# SNES_TST_Sheet3.net
KiCad netlist of a schematic drawn in Altium Designer
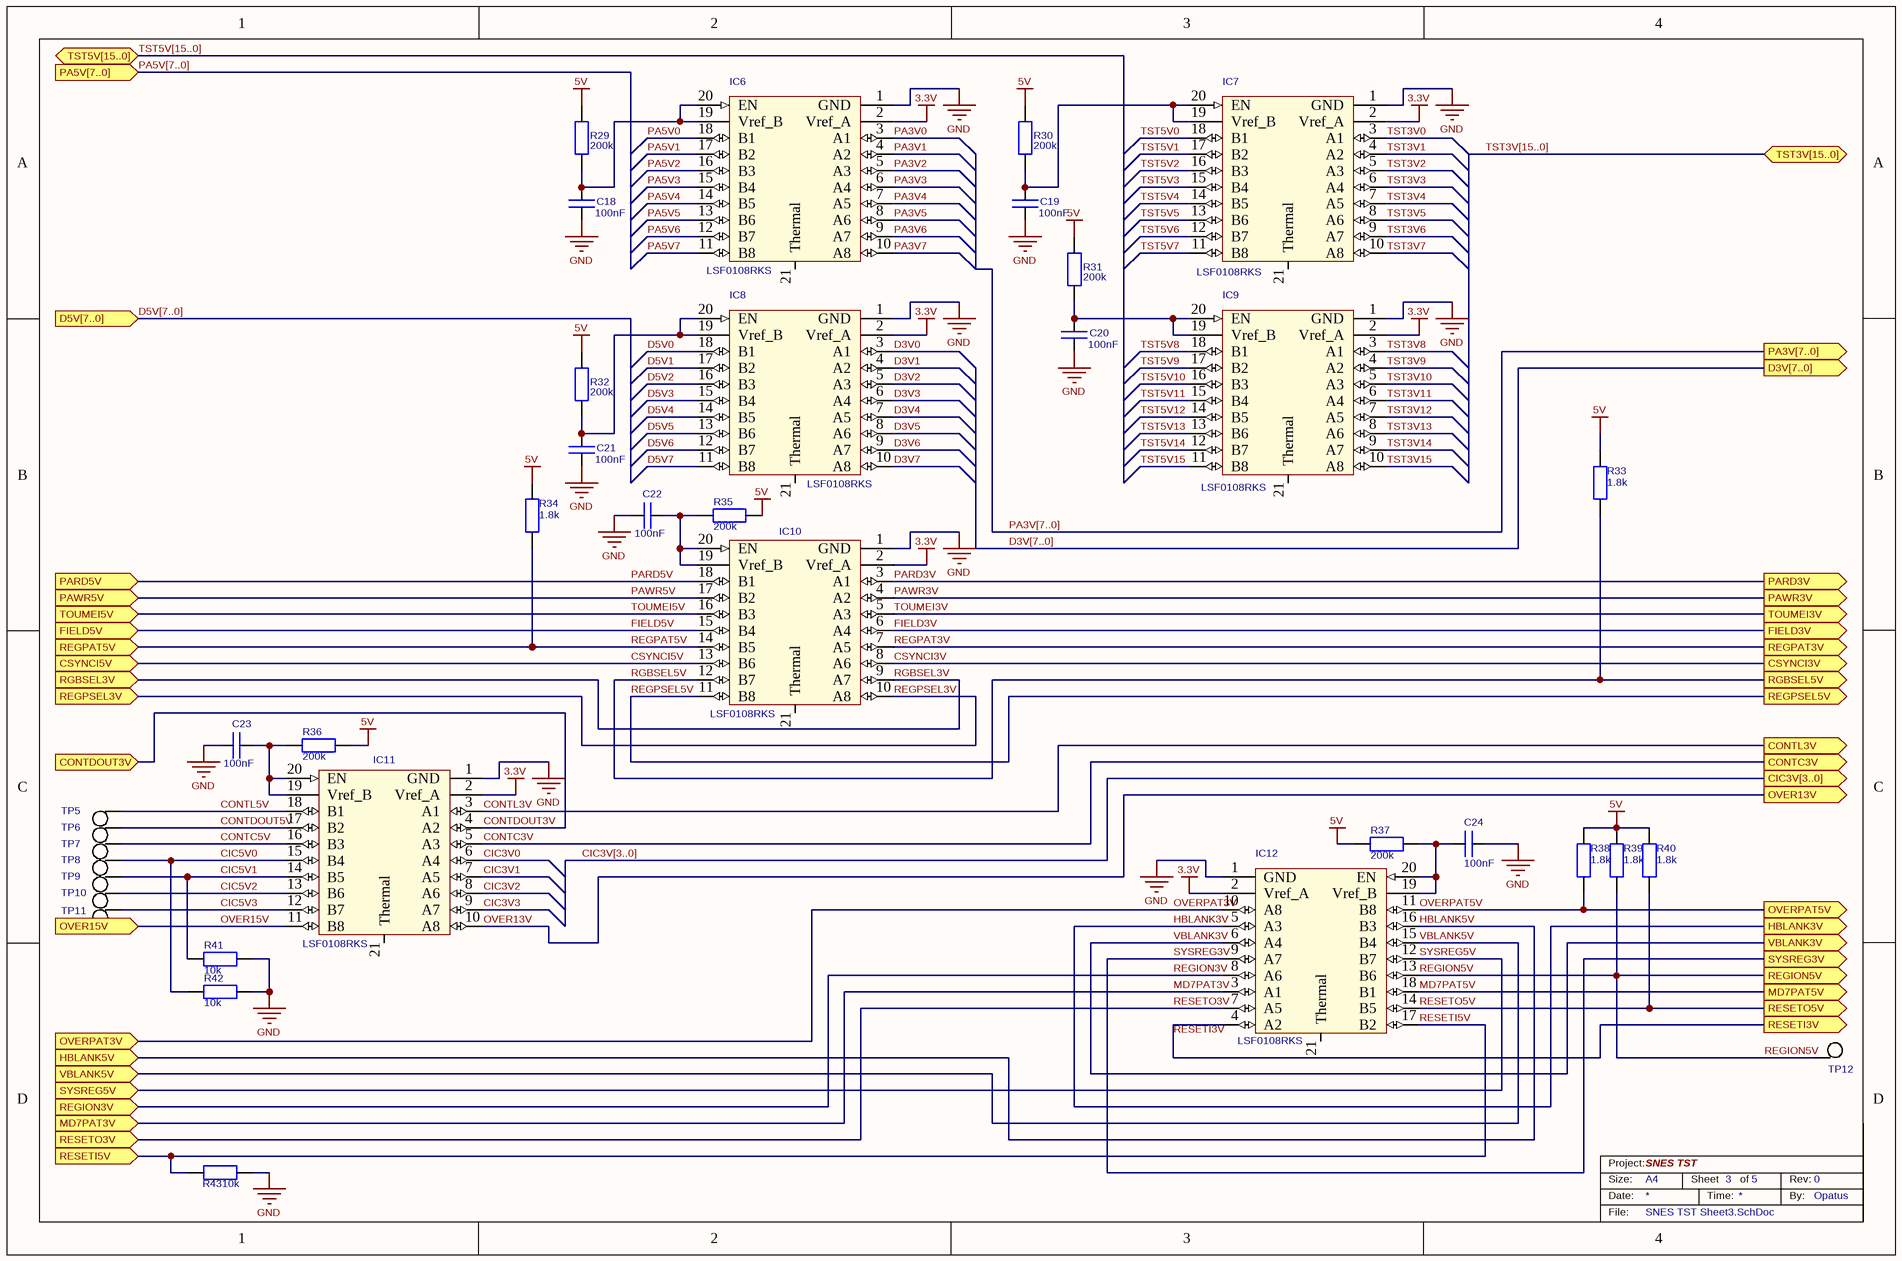
[diagram p0: SNES TST Sheet3.SchDoc]

(export (version "E")
  (design (tool "Eeschema 10.0.6"))
  (components
    (comp (ref "C18")
      (value "100nF")
      (footprint "Cap_0402_Chip")
      (fields (field (name "TOLERANCE") "+-20%"))
      (libsource (lib "PCB") (part "Capacitor"))
    )
    (comp (ref "C19")
      (value "100nF")
      (footprint "Cap_0402_Chip")
      (fields (field (name "TOLERANCE") "+-20%"))
      (libsource (lib "PCB") (part "Capacitor"))
    )
    (comp (ref "C20")
      (value "100nF")
      (footprint "Cap_0402_Chip")
      (fields (field (name "TOLERANCE") "+-20%"))
      (libsource (lib "PCB") (part "Capacitor"))
    )
    (comp (ref "C21")
      (value "100nF")
      (footprint "Cap_0402_Chip")
      (fields (field (name "TOLERANCE") "+-20%"))
      (libsource (lib "PCB") (part "Capacitor"))
    )
    (comp (ref "C22")
      (value "100nF")
      (footprint "Cap_0402_Chip")
      (fields (field (name "TOLERANCE") "+-20%"))
      (libsource (lib "PCB") (part "Capacitor"))
    )
    (comp (ref "C23")
      (value "100nF")
      (footprint "Cap_0402_Chip")
      (fields (field (name "TOLERANCE") "+-20%"))
      (libsource (lib "PCB") (part "Capacitor"))
    )
    (comp (ref "C24")
      (value "100nF")
      (footprint "Cap_0402_Chip")
      (fields (field (name "TOLERANCE") "+-20%"))
      (libsource (lib "PCB") (part "Capacitor"))
    )
    (comp (ref "IC6")
      (value "LSF0108")
      (footprint "VQFN20")
      (description "8-bit level shifter")
      (fields (field (name "MANUFACTURER_PART_NUMBER") "LSF0108RKS"))
      (libsource (lib "PCB") (part "LSF0108DCUR"))
    )
    (comp (ref "IC7")
      (value "LSF0108")
      (footprint "VQFN20")
      (description "8-bit level shifter")
      (fields (field (name "MANUFACTURER_PART_NUMBER") "LSF0108RKS"))
      (libsource (lib "PCB") (part "LSF0108DCUR"))
    )
    (comp (ref "IC8")
      (value "LSF0108")
      (footprint "VQFN20")
      (description "8-bit level shifter")
      (fields (field (name "MANUFACTURER_PART_NUMBER") "LSF0108RKS"))
      (libsource (lib "PCB") (part "LSF0108DCUR"))
    )
    (comp (ref "IC9")
      (value "LSF0108")
      (footprint "VQFN20")
      (description "8-bit level shifter")
      (fields (field (name "MANUFACTURER_PART_NUMBER") "LSF0108RKS"))
      (libsource (lib "PCB") (part "LSF0108DCUR"))
    )
    (comp (ref "IC10")
      (value "LSF0108")
      (footprint "VQFN20")
      (description "8-bit level shifter")
      (fields (field (name "MANUFACTURER_PART_NUMBER") "LSF0108RKS"))
      (libsource (lib "PCB") (part "LSF0108DCUR"))
    )
    (comp (ref "IC11")
      (value "LSF0108")
      (footprint "VQFN20")
      (description "8-bit level shifter")
      (fields (field (name "MANUFACTURER_PART_NUMBER") "LSF0108RKS"))
      (libsource (lib "PCB") (part "LSF0108DCUR"))
    )
    (comp (ref "IC12")
      (value "LSF0108")
      (footprint "VQFN20")
      (description "8-bit level shifter")
      (fields (field (name "MANUFACTURER_PART_NUMBER") "LSF0108RKS"))
      (libsource (lib "") (part "LSF0108DCUR_1"))
    )
    (comp (ref "R29")
      (value "200k")
      (footprint "Res_0402_Chip")
      (fields (field (name "TOLERANCE") "+-1%"))
      (libsource (lib "") (part "R_1"))
    )
    (comp (ref "R30")
      (value "200k")
      (footprint "Res_0402_Chip")
      (fields (field (name "TOLERANCE") "+-1%"))
      (libsource (lib "") (part "R_1"))
    )
    (comp (ref "R31")
      (value "200k")
      (footprint "Res_0402_Chip")
      (fields (field (name "TOLERANCE") "+-1%"))
      (libsource (lib "") (part "R_1"))
    )
    (comp (ref "R32")
      (value "200k")
      (footprint "Res_0402_Chip")
      (fields (field (name "TOLERANCE") "+-1%"))
      (libsource (lib "") (part "R_1"))
    )
    (comp (ref "R33")
      (value "1.8k")
      (footprint "Res_0402_Chip")
      (fields (field (name "TOLERANCE") "+-1%"))
      (libsource (lib "") (part "R_2"))
    )
    (comp (ref "R34")
      (value "1.8k")
      (footprint "Res_0402_Chip")
      (fields (field (name "TOLERANCE") "+-1%"))
      (libsource (lib "") (part "R_2"))
    )
    (comp (ref "R35")
      (value "200k")
      (footprint "Res_0402_Chip")
      (fields (field (name "TOLERANCE") "+-1%"))
      (libsource (lib "PCB") (part "R"))
    )
    (comp (ref "R36")
      (value "200k")
      (footprint "Res_0402_Chip")
      (fields (field (name "TOLERANCE") "+-1%"))
      (libsource (lib "PCB") (part "R"))
    )
    (comp (ref "R37")
      (value "200k")
      (footprint "Res_0402_Chip")
      (fields (field (name "TOLERANCE") "+-1%"))
      (libsource (lib "PCB") (part "R"))
    )
    (comp (ref "R38")
      (value "1.8k")
      (footprint "Res_0402_Chip")
      (fields (field (name "TOLERANCE") "+-1%"))
      (libsource (lib "") (part "R_2"))
    )
    (comp (ref "R39")
      (value "1.8k")
      (footprint "Res_0402_Chip")
      (fields (field (name "TOLERANCE") "+-1%"))
      (libsource (lib "") (part "R_2"))
    )
    (comp (ref "R40")
      (value "1.8k")
      (footprint "Res_0402_Chip")
      (fields (field (name "TOLERANCE") "+-1%"))
      (libsource (lib "") (part "R_2"))
    )
    (comp (ref "R41")
      (value "10k")
      (footprint "Res_0402_Chip")
      (fields (field (name "TOLERANCE") "+-1%"))
      (libsource (lib "PCB") (part "R"))
    )
    (comp (ref "R42")
      (value "10k")
      (footprint "Res_0402_Chip")
      (fields (field (name "TOLERANCE") "+-1%"))
      (libsource (lib "PCB") (part "R"))
    )
    (comp (ref "R43")
      (value "10k")
      (footprint "Res_0402_Chip")
      (fields (field (name "TOLERANCE") "+-1%"))
      (libsource (lib "") (part "R_3"))
    )
    (comp (ref "TP5")
      (value "Pin Connector")
      (footprint "Pin Connector Small")
      (libsource (lib "PCB") (part "Pin Connector"))
    )
    (comp (ref "TP6")
      (value "Pin Connector")
      (footprint "Pin Connector Small")
      (libsource (lib "PCB") (part "Pin Connector"))
    )
    (comp (ref "TP7")
      (value "Pin Connector")
      (footprint "Pin Connector Small")
      (libsource (lib "PCB") (part "Pin Connector"))
    )
    (comp (ref "TP8")
      (value "Pin Connector")
      (footprint "Pin Connector Small")
      (libsource (lib "PCB") (part "Pin Connector"))
    )
    (comp (ref "TP9")
      (value "Pin Connector")
      (footprint "Pin Connector Small")
      (libsource (lib "PCB") (part "Pin Connector"))
    )
    (comp (ref "TP10")
      (value "Pin Connector")
      (footprint "Pin Connector Small")
      (libsource (lib "PCB") (part "Pin Connector"))
    )
    (comp (ref "TP11")
      (value "Pin Connector")
      (footprint "Pin Connector Small")
      (libsource (lib "PCB") (part "Pin Connector"))
    )
    (comp (ref "TP12")
      (value "Pin Connector")
      (footprint "Pin Connector Small")
      (libsource (lib "PCB") (part "Pin Connector"))
    )
  )
  (nets
    (net (code "1") (name "/CIC3V0") (class "Default")
      (node (ref "IC11") (pin "6") (pinfunction "A4_6") (pintype "bidirectional"))
    )
    (net (code "2") (name "/CIC3V1") (class "Default")
      (node (ref "IC11") (pin "7") (pinfunction "A5_7") (pintype "bidirectional"))
    )
    (net (code "3") (name "/CIC3V2") (class "Default")
      (node (ref "IC11") (pin "8") (pinfunction "A6_8") (pintype "bidirectional"))
    )
    (net (code "4") (name "/CIC3V3") (class "Default")
      (node (ref "IC11") (pin "9") (pinfunction "A7_9") (pintype "bidirectional"))
    )
    (net (code "6") (name "/CIC5V0") (class "Default")
      (node (ref "IC11") (pin "15") (pinfunction "B4_15") (pintype "bidirectional"))
      (node (ref "R42") (pin "2") (pintype "passive"))
      (node (ref "TP8") (pin "1") (pinfunction "0_1") (pintype "passive"))
    )
    (net (code "7") (name "/CIC5V1") (class "Default")
      (node (ref "IC11") (pin "14") (pinfunction "B5_14") (pintype "bidirectional"))
      (node (ref "R41") (pin "2") (pintype "passive"))
      (node (ref "TP9") (pin "1") (pinfunction "0_1") (pintype "passive"))
    )
    (net (code "8") (name "/CIC5V2") (class "Default")
      (node (ref "IC11") (pin "13") (pinfunction "B6_13") (pintype "bidirectional"))
      (node (ref "TP10") (pin "1") (pinfunction "0_1") (pintype "passive"))
    )
    (net (code "9") (name "/CIC5V3") (class "Default")
      (node (ref "IC11") (pin "12") (pinfunction "B7_12") (pintype "bidirectional"))
      (node (ref "TP11") (pin "1") (pinfunction "0_1") (pintype "passive"))
    )
    (net (code "10") (name "/CONTC3V") (class "Default")
      (node (ref "IC11") (pin "5") (pinfunction "A3_5") (pintype "bidirectional"))
    )
    (net (code "11") (name "/CONTC5V") (class "Default")
      (node (ref "IC11") (pin "16") (pinfunction "B3_16") (pintype "bidirectional"))
      (node (ref "TP7") (pin "1") (pinfunction "0_1") (pintype "passive"))
    )
    (net (code "12") (name "/CONTDOUT3V") (class "Default")
      (node (ref "IC11") (pin "4") (pinfunction "A2_4") (pintype "bidirectional"))
    )
    (net (code "13") (name "/CONTDOUT5V") (class "Default")
      (node (ref "IC11") (pin "17") (pinfunction "B2_17") (pintype "bidirectional"))
      (node (ref "TP6") (pin "1") (pinfunction "0_1") (pintype "passive"))
    )
    (net (code "14") (name "/CONTL3V") (class "Default")
      (node (ref "IC11") (pin "3") (pinfunction "A1_3") (pintype "bidirectional"))
    )
    (net (code "15") (name "/CONTL5V") (class "Default")
      (node (ref "IC11") (pin "18") (pinfunction "B1_18") (pintype "bidirectional"))
      (node (ref "TP5") (pin "1") (pinfunction "0_1") (pintype "passive"))
    )
    (net (code "16") (name "/CSYNCI3V") (class "Default")
      (node (ref "IC10") (pin "8") (pinfunction "A6_8") (pintype "bidirectional"))
    )
    (net (code "17") (name "/CSYNCI5V") (class "Default")
      (node (ref "IC10") (pin "13") (pinfunction "B6_13") (pintype "bidirectional"))
    )
    (net (code "18") (name "/D3V0") (class "Default")
      (node (ref "IC8") (pin "3") (pinfunction "A1_3") (pintype "bidirectional"))
    )
    (net (code "19") (name "/D3V1") (class "Default")
      (node (ref "IC8") (pin "4") (pinfunction "A2_4") (pintype "bidirectional"))
    )
    (net (code "20") (name "/D3V2") (class "Default")
      (node (ref "IC8") (pin "5") (pinfunction "A3_5") (pintype "bidirectional"))
    )
    (net (code "21") (name "/D3V3") (class "Default")
      (node (ref "IC8") (pin "6") (pinfunction "A4_6") (pintype "bidirectional"))
    )
    (net (code "22") (name "/D3V4") (class "Default")
      (node (ref "IC8") (pin "7") (pinfunction "A5_7") (pintype "bidirectional"))
    )
    (net (code "23") (name "/D3V5") (class "Default")
      (node (ref "IC8") (pin "8") (pinfunction "A6_8") (pintype "bidirectional"))
    )
    (net (code "24") (name "/D3V6") (class "Default")
      (node (ref "IC8") (pin "9") (pinfunction "A7_9") (pintype "bidirectional"))
    )
    (net (code "25") (name "/D3V7") (class "Default")
      (node (ref "IC8") (pin "10") (pinfunction "A8_10") (pintype "bidirectional"))
    )
    (net (code "27") (name "/D5V0") (class "Default")
      (node (ref "IC8") (pin "18") (pinfunction "B1_18") (pintype "bidirectional"))
    )
    (net (code "28") (name "/D5V1") (class "Default")
      (node (ref "IC8") (pin "17") (pinfunction "B2_17") (pintype "bidirectional"))
    )
    (net (code "29") (name "/D5V2") (class "Default")
      (node (ref "IC8") (pin "16") (pinfunction "B3_16") (pintype "bidirectional"))
    )
    (net (code "30") (name "/D5V3") (class "Default")
      (node (ref "IC8") (pin "15") (pinfunction "B4_15") (pintype "bidirectional"))
    )
    (net (code "31") (name "/D5V4") (class "Default")
      (node (ref "IC8") (pin "14") (pinfunction "B5_14") (pintype "bidirectional"))
    )
    (net (code "32") (name "/D5V5") (class "Default")
      (node (ref "IC8") (pin "13") (pinfunction "B6_13") (pintype "bidirectional"))
    )
    (net (code "33") (name "/D5V6") (class "Default")
      (node (ref "IC8") (pin "12") (pinfunction "B7_12") (pintype "bidirectional"))
    )
    (net (code "34") (name "/D5V7") (class "Default")
      (node (ref "IC8") (pin "11") (pinfunction "B8_11") (pintype "bidirectional"))
    )
    (net (code "36") (name "/FIELD3V") (class "Default")
      (node (ref "IC10") (pin "6") (pinfunction "A4_6") (pintype "bidirectional"))
    )
    (net (code "37") (name "/FIELD5V") (class "Default")
      (node (ref "IC10") (pin "15") (pinfunction "B4_15") (pintype "bidirectional"))
    )
    (net (code "38") (name "/HBLANK3V") (class "Default")
      (node (ref "IC12") (pin "5") (pinfunction "A3_5") (pintype "bidirectional"))
    )
    (net (code "39") (name "/HBLANK5V") (class "Default")
      (node (ref "IC12") (pin "16") (pinfunction "B3_16") (pintype "bidirectional"))
    )
    (net (code "40") (name "/MD7PAT3V") (class "Default")
      (node (ref "IC12") (pin "3") (pinfunction "A1_3") (pintype "bidirectional"))
    )
    (net (code "41") (name "/MD7PAT5V") (class "Default")
      (node (ref "IC12") (pin "18") (pinfunction "B1_18") (pintype "bidirectional"))
    )
    (net (code "42") (name "/OVER13V") (class "Default")
      (node (ref "IC11") (pin "10") (pinfunction "A8_10") (pintype "bidirectional"))
    )
    (net (code "43") (name "/OVER15V") (class "Default")
      (node (ref "IC11") (pin "11") (pinfunction "B8_11") (pintype "bidirectional"))
    )
    (net (code "44") (name "/OVERPAT3V") (class "Default")
      (node (ref "IC12") (pin "10") (pinfunction "A8_10") (pintype "bidirectional"))
    )
    (net (code "45") (name "/OVERPAT5V") (class "Default")
      (node (ref "IC12") (pin "11") (pinfunction "B8_11") (pintype "bidirectional"))
      (node (ref "R38") (pin "2") (pintype "passive"))
    )
    (net (code "46") (name "/PA3V0") (class "Default")
      (node (ref "IC6") (pin "3") (pinfunction "A1_3") (pintype "bidirectional"))
    )
    (net (code "47") (name "/PA3V1") (class "Default")
      (node (ref "IC6") (pin "4") (pinfunction "A2_4") (pintype "bidirectional"))
    )
    (net (code "48") (name "/PA3V2") (class "Default")
      (node (ref "IC6") (pin "5") (pinfunction "A3_5") (pintype "bidirectional"))
    )
    (net (code "49") (name "/PA3V3") (class "Default")
      (node (ref "IC6") (pin "6") (pinfunction "A4_6") (pintype "bidirectional"))
    )
    (net (code "50") (name "/PA3V4") (class "Default")
      (node (ref "IC6") (pin "7") (pinfunction "A5_7") (pintype "bidirectional"))
    )
    (net (code "51") (name "/PA3V5") (class "Default")
      (node (ref "IC6") (pin "8") (pinfunction "A6_8") (pintype "bidirectional"))
    )
    (net (code "52") (name "/PA3V6") (class "Default")
      (node (ref "IC6") (pin "9") (pinfunction "A7_9") (pintype "bidirectional"))
    )
    (net (code "53") (name "/PA3V7") (class "Default")
      (node (ref "IC6") (pin "10") (pinfunction "A8_10") (pintype "bidirectional"))
    )
    (net (code "55") (name "/PA5V0") (class "Default")
      (node (ref "IC6") (pin "18") (pinfunction "B1_18") (pintype "bidirectional"))
    )
    (net (code "56") (name "/PA5V1") (class "Default")
      (node (ref "IC6") (pin "17") (pinfunction "B2_17") (pintype "bidirectional"))
    )
    (net (code "57") (name "/PA5V2") (class "Default")
      (node (ref "IC6") (pin "16") (pinfunction "B3_16") (pintype "bidirectional"))
    )
    (net (code "58") (name "/PA5V3") (class "Default")
      (node (ref "IC6") (pin "15") (pinfunction "B4_15") (pintype "bidirectional"))
    )
    (net (code "59") (name "/PA5V4") (class "Default")
      (node (ref "IC6") (pin "14") (pinfunction "B5_14") (pintype "bidirectional"))
    )
    (net (code "60") (name "/PA5V5") (class "Default")
      (node (ref "IC6") (pin "13") (pinfunction "B6_13") (pintype "bidirectional"))
    )
    (net (code "61") (name "/PA5V6") (class "Default")
      (node (ref "IC6") (pin "12") (pinfunction "B7_12") (pintype "bidirectional"))
    )
    (net (code "62") (name "/PA5V7") (class "Default")
      (node (ref "IC6") (pin "11") (pinfunction "B8_11") (pintype "bidirectional"))
    )
    (net (code "64") (name "/PARD3V") (class "Default")
      (node (ref "IC10") (pin "3") (pinfunction "A1_3") (pintype "bidirectional"))
    )
    (net (code "65") (name "/PARD5V") (class "Default")
      (node (ref "IC10") (pin "18") (pinfunction "B1_18") (pintype "bidirectional"))
    )
    (net (code "66") (name "/PAWR3V") (class "Default")
      (node (ref "IC10") (pin "4") (pinfunction "A2_4") (pintype "bidirectional"))
    )
    (net (code "67") (name "/PAWR5V") (class "Default")
      (node (ref "IC10") (pin "17") (pinfunction "B2_17") (pintype "bidirectional"))
    )
    (net (code "68") (name "/REGION3V") (class "Default")
      (node (ref "IC12") (pin "8") (pinfunction "A6_8") (pintype "bidirectional"))
    )
    (net (code "69") (name "/REGION5V") (class "Default")
      (node (ref "IC12") (pin "13") (pinfunction "B6_13") (pintype "bidirectional"))
      (node (ref "R39") (pin "2") (pintype "passive"))
      (node (ref "TP12") (pin "1") (pinfunction "0_1") (pintype "passive"))
    )
    (net (code "70") (name "/REGPAT3V") (class "Default")
      (node (ref "IC10") (pin "7") (pinfunction "A5_7") (pintype "bidirectional"))
    )
    (net (code "71") (name "/REGPAT5V") (class "Default")
      (node (ref "IC10") (pin "14") (pinfunction "B5_14") (pintype "bidirectional"))
      (node (ref "R34") (pin "2") (pintype "passive"))
    )
    (net (code "72") (name "/REGPSEL3V") (class "Default")
      (node (ref "IC10") (pin "10") (pinfunction "A8_10") (pintype "bidirectional"))
    )
    (net (code "73") (name "/REGPSEL5V") (class "Default")
      (node (ref "IC10") (pin "11") (pinfunction "B8_11") (pintype "bidirectional"))
    )
    (net (code "74") (name "/RESETI3V") (class "Default")
      (node (ref "IC12") (pin "4") (pinfunction "A2_4") (pintype "bidirectional"))
    )
    (net (code "75") (name "/RESETI5V") (class "Default")
      (node (ref "IC12") (pin "17") (pinfunction "B2_17") (pintype "bidirectional"))
      (node (ref "R43") (pin "1") (pintype "passive"))
    )
    (net (code "76") (name "/RESETO3V") (class "Default")
      (node (ref "IC12") (pin "7") (pinfunction "A5_7") (pintype "bidirectional"))
    )
    (net (code "77") (name "/RESETO5V") (class "Default")
      (node (ref "IC12") (pin "14") (pinfunction "B5_14") (pintype "bidirectional"))
      (node (ref "R40") (pin "2") (pintype "passive"))
    )
    (net (code "78") (name "/RGBSEL3V") (class "Default")
      (node (ref "IC10") (pin "9") (pinfunction "A7_9") (pintype "bidirectional"))
    )
    (net (code "79") (name "/RGBSEL5V") (class "Default")
      (node (ref "IC10") (pin "12") (pinfunction "B7_12") (pintype "bidirectional"))
      (node (ref "R33") (pin "2") (pintype "passive"))
    )
    (net (code "80") (name "/SYSREG3V") (class "Default")
      (node (ref "IC12") (pin "9") (pinfunction "A7_9") (pintype "bidirectional"))
    )
    (net (code "81") (name "/SYSREG5V") (class "Default")
      (node (ref "IC12") (pin "12") (pinfunction "B7_12") (pintype "bidirectional"))
    )
    (net (code "82") (name "/TOUMEI3V") (class "Default")
      (node (ref "IC10") (pin "5") (pinfunction "A3_5") (pintype "bidirectional"))
    )
    (net (code "83") (name "/TOUMEI5V") (class "Default")
      (node (ref "IC10") (pin "16") (pinfunction "B3_16") (pintype "bidirectional"))
    )
    (net (code "84") (name "/TST3V0") (class "Default")
      (node (ref "IC7") (pin "3") (pinfunction "A1_3") (pintype "bidirectional"))
    )
    (net (code "85") (name "/TST3V1") (class "Default")
      (node (ref "IC7") (pin "4") (pinfunction "A2_4") (pintype "bidirectional"))
    )
    (net (code "86") (name "/TST3V2") (class "Default")
      (node (ref "IC7") (pin "5") (pinfunction "A3_5") (pintype "bidirectional"))
    )
    (net (code "87") (name "/TST3V3") (class "Default")
      (node (ref "IC7") (pin "6") (pinfunction "A4_6") (pintype "bidirectional"))
    )
    (net (code "88") (name "/TST3V4") (class "Default")
      (node (ref "IC7") (pin "7") (pinfunction "A5_7") (pintype "bidirectional"))
    )
    (net (code "89") (name "/TST3V5") (class "Default")
      (node (ref "IC7") (pin "8") (pinfunction "A6_8") (pintype "bidirectional"))
    )
    (net (code "90") (name "/TST3V6") (class "Default")
      (node (ref "IC7") (pin "9") (pinfunction "A7_9") (pintype "bidirectional"))
    )
    (net (code "91") (name "/TST3V7") (class "Default")
      (node (ref "IC7") (pin "10") (pinfunction "A8_10") (pintype "bidirectional"))
    )
    (net (code "92") (name "/TST3V8") (class "Default")
      (node (ref "IC9") (pin "3") (pinfunction "A1_3") (pintype "bidirectional"))
    )
    (net (code "93") (name "/TST3V9") (class "Default")
      (node (ref "IC9") (pin "4") (pinfunction "A2_4") (pintype "bidirectional"))
    )
    (net (code "94") (name "/TST3V10") (class "Default")
      (node (ref "IC9") (pin "5") (pinfunction "A3_5") (pintype "bidirectional"))
    )
    (net (code "95") (name "/TST3V11") (class "Default")
      (node (ref "IC9") (pin "6") (pinfunction "A4_6") (pintype "bidirectional"))
    )
    (net (code "96") (name "/TST3V12") (class "Default")
      (node (ref "IC9") (pin "7") (pinfunction "A5_7") (pintype "bidirectional"))
    )
    (net (code "97") (name "/TST3V13") (class "Default")
      (node (ref "IC9") (pin "8") (pinfunction "A6_8") (pintype "bidirectional"))
    )
    (net (code "98") (name "/TST3V14") (class "Default")
      (node (ref "IC9") (pin "9") (pinfunction "A7_9") (pintype "bidirectional"))
    )
    (net (code "99") (name "/TST3V15") (class "Default")
      (node (ref "IC9") (pin "10") (pinfunction "A8_10") (pintype "bidirectional"))
    )
    (net (code "101") (name "/TST5V0") (class "Default")
      (node (ref "IC7") (pin "18") (pinfunction "B1_18") (pintype "bidirectional"))
    )
    (net (code "102") (name "/TST5V1") (class "Default")
      (node (ref "IC7") (pin "17") (pinfunction "B2_17") (pintype "bidirectional"))
    )
    (net (code "103") (name "/TST5V2") (class "Default")
      (node (ref "IC7") (pin "16") (pinfunction "B3_16") (pintype "bidirectional"))
    )
    (net (code "104") (name "/TST5V3") (class "Default")
      (node (ref "IC7") (pin "15") (pinfunction "B4_15") (pintype "bidirectional"))
    )
    (net (code "105") (name "/TST5V4") (class "Default")
      (node (ref "IC7") (pin "14") (pinfunction "B5_14") (pintype "bidirectional"))
    )
    (net (code "106") (name "/TST5V5") (class "Default")
      (node (ref "IC7") (pin "13") (pinfunction "B6_13") (pintype "bidirectional"))
    )
    (net (code "107") (name "/TST5V6") (class "Default")
      (node (ref "IC7") (pin "12") (pinfunction "B7_12") (pintype "bidirectional"))
    )
    (net (code "108") (name "/TST5V7") (class "Default")
      (node (ref "IC7") (pin "11") (pinfunction "B8_11") (pintype "bidirectional"))
    )
    (net (code "109") (name "/TST5V8") (class "Default")
      (node (ref "IC9") (pin "18") (pinfunction "B1_18") (pintype "bidirectional"))
    )
    (net (code "110") (name "/TST5V9") (class "Default")
      (node (ref "IC9") (pin "17") (pinfunction "B2_17") (pintype "bidirectional"))
    )
    (net (code "111") (name "/TST5V10") (class "Default")
      (node (ref "IC9") (pin "16") (pinfunction "B3_16") (pintype "bidirectional"))
    )
    (net (code "112") (name "/TST5V11") (class "Default")
      (node (ref "IC9") (pin "15") (pinfunction "B4_15") (pintype "bidirectional"))
    )
    (net (code "113") (name "/TST5V12") (class "Default")
      (node (ref "IC9") (pin "14") (pinfunction "B5_14") (pintype "bidirectional"))
    )
    (net (code "114") (name "/TST5V13") (class "Default")
      (node (ref "IC9") (pin "13") (pinfunction "B6_13") (pintype "bidirectional"))
    )
    (net (code "115") (name "/TST5V14") (class "Default")
      (node (ref "IC9") (pin "12") (pinfunction "B7_12") (pintype "bidirectional"))
    )
    (net (code "116") (name "/TST5V15") (class "Default")
      (node (ref "IC9") (pin "11") (pinfunction "B8_11") (pintype "bidirectional"))
    )
    (net (code "118") (name "/VBLANK3V") (class "Default")
      (node (ref "IC12") (pin "6") (pinfunction "A4_6") (pintype "bidirectional"))
    )
    (net (code "119") (name "/VBLANK5V") (class "Default")
      (node (ref "IC12") (pin "15") (pinfunction "B4_15") (pintype "bidirectional"))
    )
    (net (code "120") (name "3.3V") (class "Default")
      (node (ref "IC10") (pin "2") (pinfunction "Vref_A_2") (pintype "power_in"))
      (node (ref "IC11") (pin "2") (pinfunction "Vref_A_2") (pintype "power_in"))
      (node (ref "IC12") (pin "2") (pinfunction "Vref_A_2") (pintype "power_in"))
      (node (ref "IC6") (pin "2") (pinfunction "Vref_A_2") (pintype "power_in"))
      (node (ref "IC7") (pin "2") (pinfunction "Vref_A_2") (pintype "power_in"))
      (node (ref "IC8") (pin "2") (pinfunction "Vref_A_2") (pintype "power_in"))
      (node (ref "IC9") (pin "2") (pinfunction "Vref_A_2") (pintype "power_in"))
    )
    (net (code "121") (name "5V") (class "Default")
      (node (ref "R29") (pin "2") (pintype "passive"))
      (node (ref "R30") (pin "2") (pintype "passive"))
      (node (ref "R31") (pin "2") (pintype "passive"))
      (node (ref "R32") (pin "2") (pintype "passive"))
      (node (ref "R33") (pin "1") (pintype "passive"))
      (node (ref "R34") (pin "1") (pintype "passive"))
      (node (ref "R35") (pin "1") (pintype "passive"))
      (node (ref "R36") (pin "1") (pintype "passive"))
      (node (ref "R37") (pin "2") (pintype "passive"))
      (node (ref "R38") (pin "1") (pintype "passive"))
      (node (ref "R39") (pin "1") (pintype "passive"))
      (node (ref "R40") (pin "1") (pintype "passive"))
    )
    (net (code "122") (name "GND") (class "Default")
      (node (ref "C18") (pin "2") (pintype "passive"))
      (node (ref "C19") (pin "2") (pintype "passive"))
      (node (ref "C20") (pin "2") (pintype "passive"))
      (node (ref "C21") (pin "2") (pintype "passive"))
      (node (ref "C22") (pin "1") (pintype "passive"))
      (node (ref "C23") (pin "1") (pintype "passive"))
      (node (ref "C24") (pin "2") (pintype "passive"))
      (node (ref "IC10") (pin "1") (pinfunction "GND_1") (pintype "power_in"))
      (node (ref "IC11") (pin "1") (pinfunction "GND_1") (pintype "power_in"))
      (node (ref "IC12") (pin "1") (pinfunction "GND_1") (pintype "power_in"))
      (node (ref "IC6") (pin "1") (pinfunction "GND_1") (pintype "power_in"))
      (node (ref "IC7") (pin "1") (pinfunction "GND_1") (pintype "power_in"))
      (node (ref "IC8") (pin "1") (pinfunction "GND_1") (pintype "power_in"))
      (node (ref "IC9") (pin "1") (pinfunction "GND_1") (pintype "power_in"))
      (node (ref "R41") (pin "1") (pintype "passive"))
      (node (ref "R42") (pin "1") (pintype "passive"))
      (node (ref "R43") (pin "2") (pintype "passive"))
    )
    (net (code "123") (name "Net-(IC6-EN)") (class "Default")
      (node (ref "C18") (pin "1") (pintype "passive"))
      (node (ref "IC6") (pin "19") (pinfunction "Vref_B_19") (pintype "power_in"))
      (node (ref "IC6") (pin "20") (pinfunction "EN_20") (pintype "input"))
      (node (ref "R29") (pin "1") (pintype "passive"))
    )
    (net (code "124") (name "Net-(IC7-EN)") (class "Default")
      (node (ref "C19") (pin "1") (pintype "passive"))
      (node (ref "IC7") (pin "19") (pinfunction "Vref_B_19") (pintype "power_in"))
      (node (ref "IC7") (pin "20") (pinfunction "EN_20") (pintype "input"))
      (node (ref "R30") (pin "1") (pintype "passive"))
    )
    (net (code "125") (name "Net-(IC8-EN)") (class "Default")
      (node (ref "C21") (pin "1") (pintype "passive"))
      (node (ref "IC8") (pin "19") (pinfunction "Vref_B_19") (pintype "power_in"))
      (node (ref "IC8") (pin "20") (pinfunction "EN_20") (pintype "input"))
      (node (ref "R32") (pin "1") (pintype "passive"))
    )
    (net (code "126") (name "Net-(IC9-EN)") (class "Default")
      (node (ref "C20") (pin "1") (pintype "passive"))
      (node (ref "IC9") (pin "19") (pinfunction "Vref_B_19") (pintype "power_in"))
      (node (ref "IC9") (pin "20") (pinfunction "EN_20") (pintype "input"))
      (node (ref "R31") (pin "1") (pintype "passive"))
    )
    (net (code "127") (name "Net-(IC10-EN)") (class "Default")
      (node (ref "C22") (pin "2") (pintype "passive"))
      (node (ref "IC10") (pin "19") (pinfunction "Vref_B_19") (pintype "power_in"))
      (node (ref "IC10") (pin "20") (pinfunction "EN_20") (pintype "input"))
      (node (ref "R35") (pin "2") (pintype "passive"))
    )
    (net (code "128") (name "Net-(IC11-EN)") (class "Default")
      (node (ref "C23") (pin "2") (pintype "passive"))
      (node (ref "IC11") (pin "19") (pinfunction "Vref_B_19") (pintype "power_in"))
      (node (ref "IC11") (pin "20") (pinfunction "EN_20") (pintype "input"))
      (node (ref "R36") (pin "2") (pintype "passive"))
    )
    (net (code "129") (name "Net-(IC12-EN)") (class "Default")
      (node (ref "C24") (pin "1") (pintype "passive"))
      (node (ref "IC12") (pin "19") (pinfunction "Vref_B_19") (pintype "power_in"))
      (node (ref "IC12") (pin "20") (pinfunction "EN_20") (pintype "input"))
      (node (ref "R37") (pin "1") (pintype "passive"))
    )
    (net (code "130") (name "unconnected-(IC6-Thermal-Pad21)") (class "Default")
      (node (ref "IC6") (pin "21") (pinfunction "Thermal_21") (pintype "passive"))
    )
    (net (code "131") (name "unconnected-(IC7-Thermal-Pad21)") (class "Default")
      (node (ref "IC7") (pin "21") (pinfunction "Thermal_21") (pintype "passive"))
    )
    (net (code "132") (name "unconnected-(IC8-Thermal-Pad21)") (class "Default")
      (node (ref "IC8") (pin "21") (pinfunction "Thermal_21") (pintype "passive"))
    )
    (net (code "133") (name "unconnected-(IC9-Thermal-Pad21)") (class "Default")
      (node (ref "IC9") (pin "21") (pinfunction "Thermal_21") (pintype "passive"))
    )
    (net (code "134") (name "unconnected-(IC10-Thermal-Pad21)") (class "Default")
      (node (ref "IC10") (pin "21") (pinfunction "Thermal_21") (pintype "passive"))
    )
    (net (code "135") (name "unconnected-(IC11-Thermal-Pad21)") (class "Default")
      (node (ref "IC11") (pin "21") (pinfunction "Thermal_21") (pintype "passive"))
    )
    (net (code "136") (name "unconnected-(IC12-Thermal-Pad21)") (class "Default")
      (node (ref "IC12") (pin "21") (pinfunction "Thermal_21") (pintype "passive"))
    )
  )
)
